# KeepUntil-v1_0_1.net
KiCad netlist of a schematic drawn in EAGLE
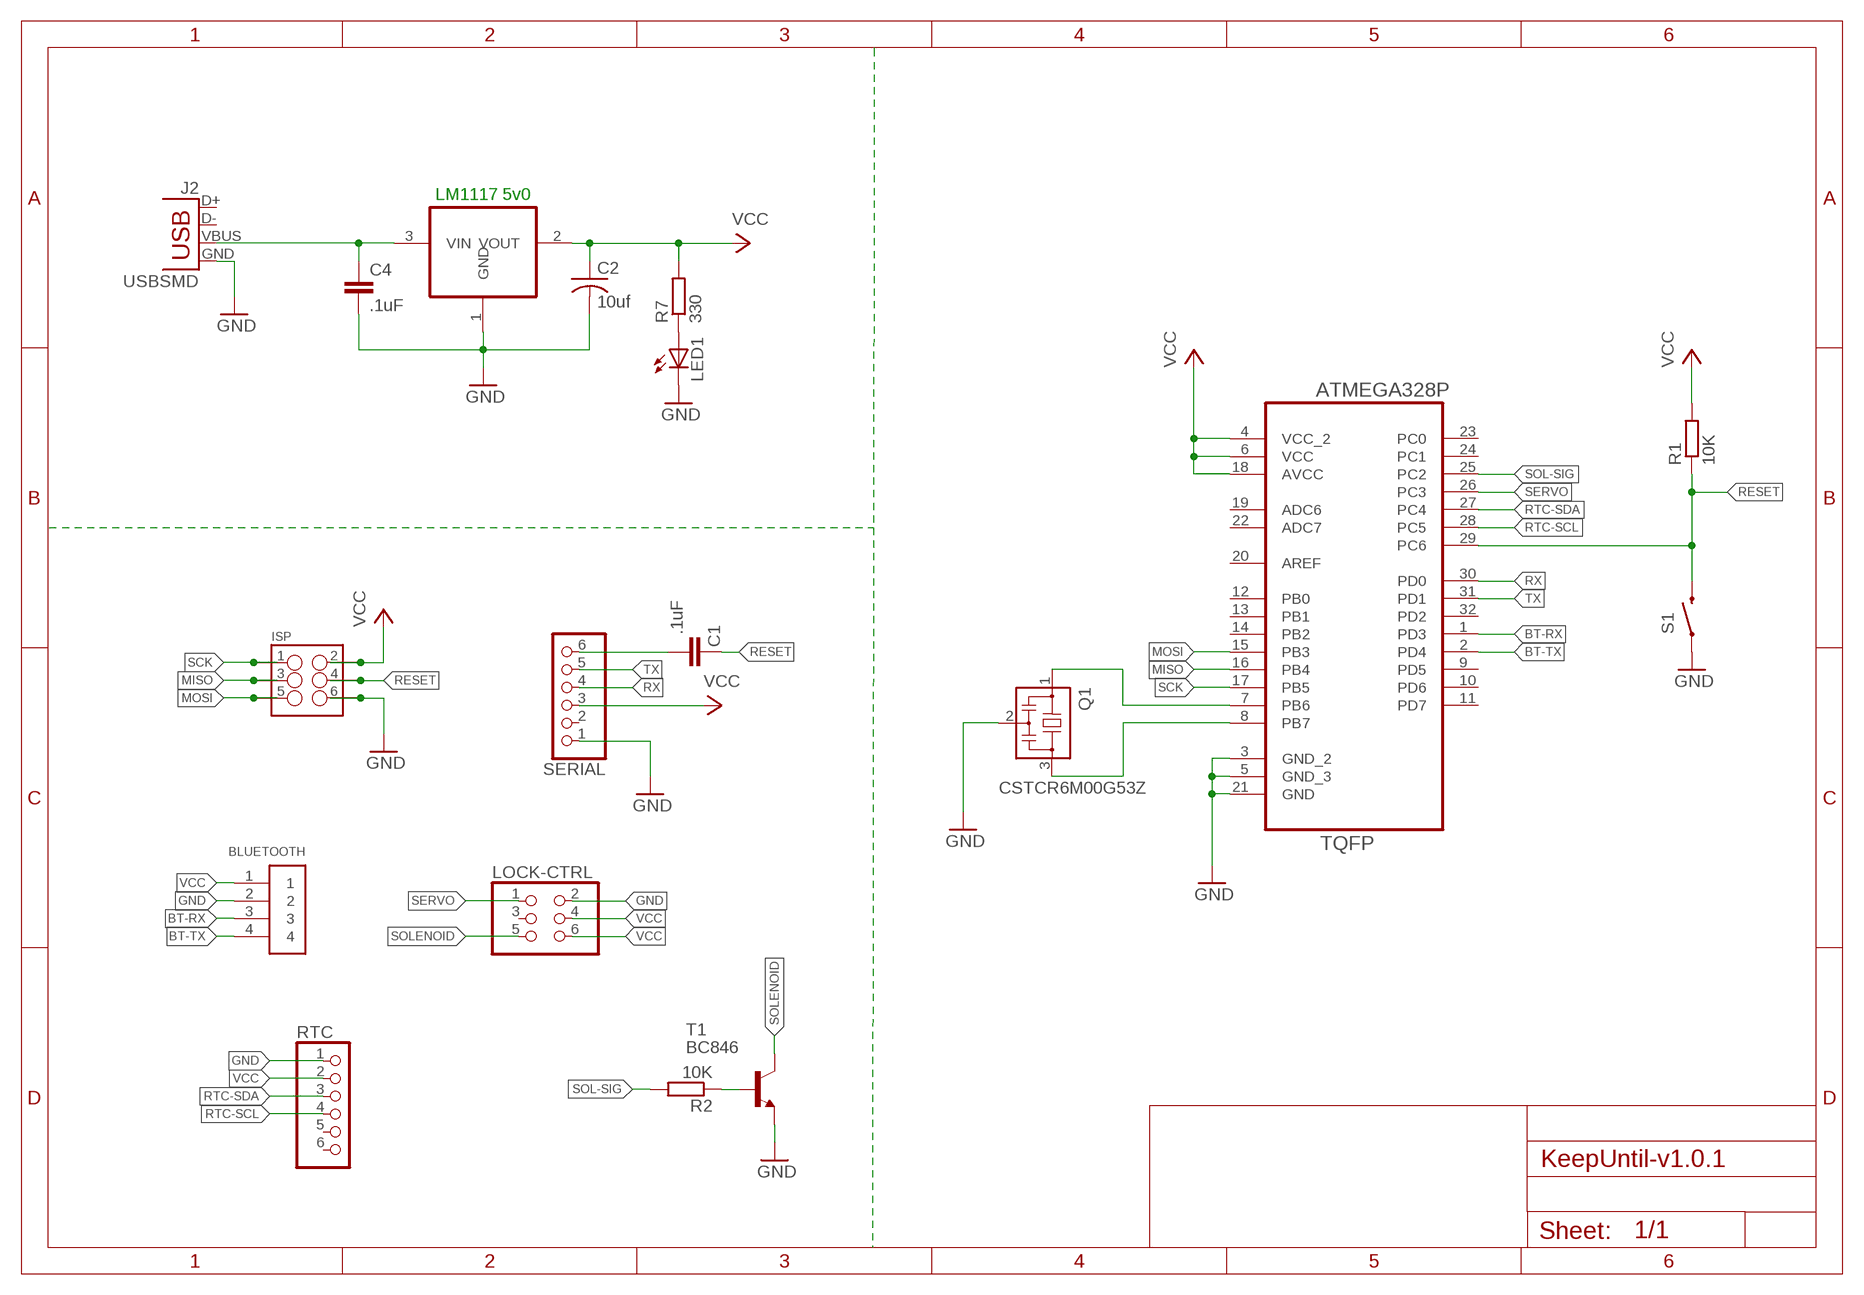
[diagram p0: schematic, sheet 1]

(export (version "E")
  (design (tool "Eeschema 10.0.6"))
  (components
    (comp (ref "BLUETOOTH")
      (value "1X4-CLEANBIG")
      (footprint "eagle-import:1X04-CLEANBIG")
      (libsource (lib "eagle-import") (part "1X4-CLEANBIG"))
    )
    (comp (ref "C1")
      (value ".1uF")
      (footprint "eagle-import:C0805")
      (libsource (lib "eagle-import") (part "C-EUC0805"))
    )
    (comp (ref "C2")
      (value "10uf")
      (footprint "eagle-import:C1206")
      (libsource (lib "eagle-import") (part "C-USC1206"))
    )
    (comp (ref "C4")
      (value ".1uF")
      (footprint "eagle-import:C0805")
      (libsource (lib "eagle-import") (part "C-EUC0805"))
    )
    (comp (ref "IC2")
      (value "REG1117")
      (footprint "eagle-import:SOT223")
      (fields (field (name "MPN") "LM1117 3v3"))
      (libsource (lib "eagle-import") (part "REG1117"))
    )
    (comp (ref "ISP")
      (value "M03X2SHROUD")
      (footprint "eagle-import:2X3-SHROUDED")
      (libsource (lib "eagle-import") (part "M03X2SHROUD"))
    )
    (comp (ref "J2")
      (value "USBSMD")
      (footprint "eagle-import:USB-MINIB")
      (libsource (lib "eagle-import") (part "USBSMD"))
    )
    (comp (ref "LED1")
      (value "LEDSMT1206")
      (footprint "eagle-import:1206")
      (libsource (lib "eagle-import") (part "LEDSMT1206"))
    )
    (comp (ref "LOCK-CTRL")
      (value "PINHD-2X3")
      (footprint "eagle-import:2X03")
      (libsource (lib "eagle-import") (part "PINHD-2X3"))
    )
    (comp (ref "Q1")
      (value "CSTCR6M00G53Z")
      (footprint "eagle-import:CSTCR6M")
      (fields (field (name "MPN") "CSTCR6M00G53-R0"))
      (libsource (lib "eagle-import") (part "CSTCR6M00G53Z"))
    )
    (comp (ref "R1")
      (value "10K")
      (footprint "eagle-import:R0805")
      (libsource (lib "eagle-import") (part "R-EU_R0805"))
    )
    (comp (ref "R2")
      (value "10K")
      (footprint "eagle-import:R0805")
      (libsource (lib "eagle-import") (part "R-EU_R0805"))
    )
    (comp (ref "R7")
      (value "330")
      (footprint "eagle-import:R0805")
      (libsource (lib "eagle-import") (part "R-EU_R0805"))
    )
    (comp (ref "RTC")
      (value "PINHD-1X6CLEAN")
      (footprint "eagle-import:1X06-CLEAN")
      (libsource (lib "eagle-import") (part "PINHD-1X6CLEAN"))
    )
    (comp (ref "S1")
      (value "SWITCH-MOMENTARY-2SMD-1101NE")
      (footprint "eagle-import:TACTILE-SWITCH-1101NE")
      (libsource (lib "eagle-import") (part "SWITCH-MOMENTARY-2SMD-1101NE"))
    )
    (comp (ref "SERIAL")
      (value "PINHD-1X6CLEAN")
      (footprint "eagle-import:1X06-CLEAN")
      (libsource (lib "eagle-import") (part "PINHD-1X6CLEAN"))
    )
    (comp (ref "T1")
      (value "BC846")
      (footprint "eagle-import:SOT23")
      (libsource (lib "eagle-import") (part "BC846"))
    )
    (comp (ref "U1")
      (value "ATMEGA328P-AU")
      (footprint "eagle-import:QFP80P900X900X120-32N")
      (libsource (lib "eagle-import") (part "ATMEGA328P-AU"))
    )
  )
  (nets
    (net (code "1") (name "BT-RX") (class "Default")
      (node (ref "BLUETOOTH") (pin "3") (pinfunction "3_3") (pintype "bidirectional"))
      (node (ref "U1") (pin "1") (pinfunction "PD3_1") (pintype "bidirectional"))
    )
    (net (code "2") (name "BT-TX") (class "Default")
      (node (ref "BLUETOOTH") (pin "4") (pinfunction "4_4") (pintype "bidirectional"))
      (node (ref "U1") (pin "2") (pinfunction "PD4_2") (pintype "bidirectional"))
    )
    (net (code "3") (name "GND") (class "Default")
      (node (ref "BLUETOOTH") (pin "2") (pinfunction "2_2") (pintype "bidirectional"))
      (node (ref "C2") (pin "2") (pinfunction "2_2") (pintype "passive"))
      (node (ref "C4") (pin "2") (pinfunction "2_2") (pintype "passive"))
      (node (ref "IC2") (pin "1") (pinfunction "GND_1") (pintype "power_in"))
      (node (ref "ISP") (pin "6") (pinfunction "6_6") (pintype "bidirectional"))
      (node (ref "J2") (pin "GND") (pinfunction "GND_GND") (pintype "bidirectional"))
      (node (ref "LED1") (pin "C") (pinfunction "C_C") (pintype "passive"))
      (node (ref "LOCK-CTRL") (pin "2") (pinfunction "2_2") (pintype "passive"))
      (node (ref "Q1") (pin "2") (pinfunction "2_2") (pintype "passive"))
      (node (ref "RTC") (pin "1") (pinfunction "1_1") (pintype "passive"))
      (node (ref "S1") (pin "1") (pinfunction "1_1") (pintype "passive"))
      (node (ref "SERIAL") (pin "1") (pinfunction "1_1") (pintype "passive"))
      (node (ref "T1") (pin "2") (pinfunction "E_2") (pintype "passive"))
      (node (ref "U1") (pin "21") (pinfunction "GND_21") (pintype "passive"))
      (node (ref "U1") (pin "3") (pinfunction "GND_2_3") (pintype "passive"))
      (node (ref "U1") (pin "5") (pinfunction "GND_3_5") (pintype "passive"))
    )
    (net (code "4") (name "MISO") (class "Default")
      (node (ref "ISP") (pin "3") (pinfunction "3_3") (pintype "bidirectional"))
      (node (ref "U1") (pin "16") (pinfunction "PB4_16") (pintype "bidirectional"))
    )
    (net (code "5") (name "MOSI") (class "Default")
      (node (ref "ISP") (pin "5") (pinfunction "5_5") (pintype "bidirectional"))
      (node (ref "U1") (pin "15") (pinfunction "PB3_15") (pintype "bidirectional"))
    )
    (net (code "6") (name "Net-(C1-Pad2)") (class "Default")
      (node (ref "C1") (pin "2") (pinfunction "2_2") (pintype "passive"))
      (node (ref "SERIAL") (pin "6") (pinfunction "6_6") (pintype "passive"))
    )
    (net (code "7") (name "Net-(IC2-VIN)") (class "Default")
      (node (ref "C4") (pin "1") (pinfunction "1_1") (pintype "passive"))
      (node (ref "IC2") (pin "3") (pinfunction "VIN_3") (pintype "input"))
      (node (ref "J2") (pin "VBUS") (pinfunction "VBUS_VBUS") (pintype "bidirectional"))
    )
    (net (code "8") (name "Net-(LED1-PadA)") (class "Default")
      (node (ref "LED1") (pin "A") (pinfunction "A_A") (pintype "passive"))
      (node (ref "R7") (pin "1") (pinfunction "1_1") (pintype "passive"))
    )
    (net (code "9") (name "Net-(T1-B)") (class "Default")
      (node (ref "R2") (pin "1") (pinfunction "1_1") (pintype "passive"))
      (node (ref "T1") (pin "1") (pinfunction "B_1") (pintype "passive"))
    )
    (net (code "10") (name "Net-(U1-PB6)") (class "Default")
      (node (ref "Q1") (pin "1") (pinfunction "1_1") (pintype "passive"))
      (node (ref "U1") (pin "7") (pinfunction "PB6_7") (pintype "bidirectional"))
    )
    (net (code "11") (name "Net-(U1-PB7)") (class "Default")
      (node (ref "Q1") (pin "3") (pinfunction "3_3") (pintype "passive"))
      (node (ref "U1") (pin "8") (pinfunction "PB7_8") (pintype "bidirectional"))
    )
    (net (code "12") (name "RESET") (class "Default")
      (node (ref "C1") (pin "1") (pinfunction "1_1") (pintype "passive"))
      (node (ref "ISP") (pin "4") (pinfunction "4_4") (pintype "bidirectional"))
      (node (ref "R1") (pin "1") (pinfunction "1_1") (pintype "passive"))
      (node (ref "S1") (pin "2") (pinfunction "2_2") (pintype "passive"))
      (node (ref "U1") (pin "29") (pinfunction "PC6_29") (pintype "bidirectional"))
    )
    (net (code "13") (name "RTC-SCL") (class "Default")
      (node (ref "RTC") (pin "4") (pinfunction "4_4") (pintype "passive"))
      (node (ref "U1") (pin "28") (pinfunction "PC5_28") (pintype "bidirectional"))
    )
    (net (code "14") (name "RTC-SDA") (class "Default")
      (node (ref "RTC") (pin "3") (pinfunction "3_3") (pintype "passive"))
      (node (ref "U1") (pin "27") (pinfunction "PC4_27") (pintype "bidirectional"))
    )
    (net (code "15") (name "RX") (class "Default")
      (node (ref "SERIAL") (pin "4") (pinfunction "4_4") (pintype "passive"))
      (node (ref "U1") (pin "30") (pinfunction "PD0_30") (pintype "bidirectional"))
    )
    (net (code "16") (name "SCK") (class "Default")
      (node (ref "ISP") (pin "1") (pinfunction "1_1") (pintype "bidirectional"))
      (node (ref "U1") (pin "17") (pinfunction "PB5_17") (pintype "bidirectional"))
    )
    (net (code "17") (name "SERVO") (class "Default")
      (node (ref "LOCK-CTRL") (pin "1") (pinfunction "1_1") (pintype "passive"))
      (node (ref "U1") (pin "26") (pinfunction "PC3_26") (pintype "bidirectional"))
    )
    (net (code "18") (name "SOL-SIG") (class "Default")
      (node (ref "R2") (pin "2") (pinfunction "2_2") (pintype "passive"))
      (node (ref "U1") (pin "25") (pinfunction "PC2_25") (pintype "bidirectional"))
    )
    (net (code "19") (name "SOLENOID") (class "Default")
      (node (ref "LOCK-CTRL") (pin "5") (pinfunction "5_5") (pintype "passive"))
      (node (ref "T1") (pin "3") (pinfunction "C_3") (pintype "passive"))
    )
    (net (code "20") (name "TX") (class "Default")
      (node (ref "SERIAL") (pin "5") (pinfunction "5_5") (pintype "passive"))
      (node (ref "U1") (pin "31") (pinfunction "PD1_31") (pintype "bidirectional"))
    )
    (net (code "21") (name "VCC") (class "Default")
      (node (ref "BLUETOOTH") (pin "1") (pinfunction "1_1") (pintype "bidirectional"))
      (node (ref "C2") (pin "1") (pinfunction "1_1") (pintype "passive"))
      (node (ref "IC2") (pin "2") (pinfunction "VOUT_2") (pintype "output"))
      (node (ref "ISP") (pin "2") (pinfunction "2_2") (pintype "bidirectional"))
      (node (ref "LOCK-CTRL") (pin "4") (pinfunction "4_4") (pintype "passive"))
      (node (ref "LOCK-CTRL") (pin "6") (pinfunction "6_6") (pintype "passive"))
      (node (ref "R1") (pin "2") (pinfunction "2_2") (pintype "passive"))
      (node (ref "R7") (pin "2") (pinfunction "2_2") (pintype "passive"))
      (node (ref "RTC") (pin "2") (pinfunction "2_2") (pintype "passive"))
      (node (ref "SERIAL") (pin "3") (pinfunction "3_3") (pintype "passive"))
      (node (ref "U1") (pin "18") (pinfunction "AVCC_18") (pintype "power_in"))
      (node (ref "U1") (pin "4") (pinfunction "VCC_2_4") (pintype "power_in"))
      (node (ref "U1") (pin "6") (pinfunction "VCC_6") (pintype "power_in"))
    )
    (net (code "22") (name "unconnected-(J2-PadD+)") (class "Default")
      (node (ref "J2") (pin "D+") (pinfunction "D+_D+") (pintype "bidirectional"))
    )
    (net (code "23") (name "unconnected-(J2-PadD-)") (class "Default")
      (node (ref "J2") (pin "D-") (pinfunction "D-_D-") (pintype "bidirectional"))
    )
    (net (code "24") (name "unconnected-(LOCK-CTRL-Pad3)") (class "Default")
      (node (ref "LOCK-CTRL") (pin "3") (pinfunction "3_3") (pintype "passive"))
    )
    (net (code "25") (name "unconnected-(RTC-Pad5)") (class "Default")
      (node (ref "RTC") (pin "5") (pinfunction "5_5") (pintype "passive"))
    )
    (net (code "26") (name "unconnected-(RTC-Pad6)") (class "Default")
      (node (ref "RTC") (pin "6") (pinfunction "6_6") (pintype "passive"))
    )
    (net (code "27") (name "unconnected-(SERIAL-Pad2)") (class "Default")
      (node (ref "SERIAL") (pin "2") (pinfunction "2_2") (pintype "passive"))
    )
    (net (code "28") (name "unconnected-(U1-ADC6-Pad19)") (class "Default")
      (node (ref "U1") (pin "19") (pinfunction "ADC6_19") (pintype "input"))
    )
    (net (code "29") (name "unconnected-(U1-ADC7-Pad22)") (class "Default")
      (node (ref "U1") (pin "22") (pinfunction "ADC7_22") (pintype "input"))
    )
    (net (code "30") (name "unconnected-(U1-AREF-Pad20)") (class "Default")
      (node (ref "U1") (pin "20") (pinfunction "AREF_20") (pintype "input"))
    )
    (net (code "31") (name "unconnected-(U1-PB0-Pad12)") (class "Default")
      (node (ref "U1") (pin "12") (pinfunction "PB0_12") (pintype "bidirectional"))
    )
    (net (code "32") (name "unconnected-(U1-PB1-Pad13)") (class "Default")
      (node (ref "U1") (pin "13") (pinfunction "PB1_13") (pintype "bidirectional"))
    )
    (net (code "33") (name "unconnected-(U1-PB2-Pad14)") (class "Default")
      (node (ref "U1") (pin "14") (pinfunction "PB2_14") (pintype "bidirectional"))
    )
    (net (code "34") (name "unconnected-(U1-PC0-Pad23)") (class "Default")
      (node (ref "U1") (pin "23") (pinfunction "PC0_23") (pintype "bidirectional"))
    )
    (net (code "35") (name "unconnected-(U1-PC1-Pad24)") (class "Default")
      (node (ref "U1") (pin "24") (pinfunction "PC1_24") (pintype "bidirectional"))
    )
    (net (code "36") (name "unconnected-(U1-PD2-Pad32)") (class "Default")
      (node (ref "U1") (pin "32") (pinfunction "PD2_32") (pintype "bidirectional"))
    )
    (net (code "37") (name "unconnected-(U1-PD5-Pad9)") (class "Default")
      (node (ref "U1") (pin "9") (pinfunction "PD5_9") (pintype "bidirectional"))
    )
    (net (code "38") (name "unconnected-(U1-PD6-Pad10)") (class "Default")
      (node (ref "U1") (pin "10") (pinfunction "PD6_10") (pintype "bidirectional"))
    )
    (net (code "39") (name "unconnected-(U1-PD7-Pad11)") (class "Default")
      (node (ref "U1") (pin "11") (pinfunction "PD7_11") (pintype "bidirectional"))
    )
  )
)
